# camara.net
KiCad netlist of a schematic drawn in EAGLE
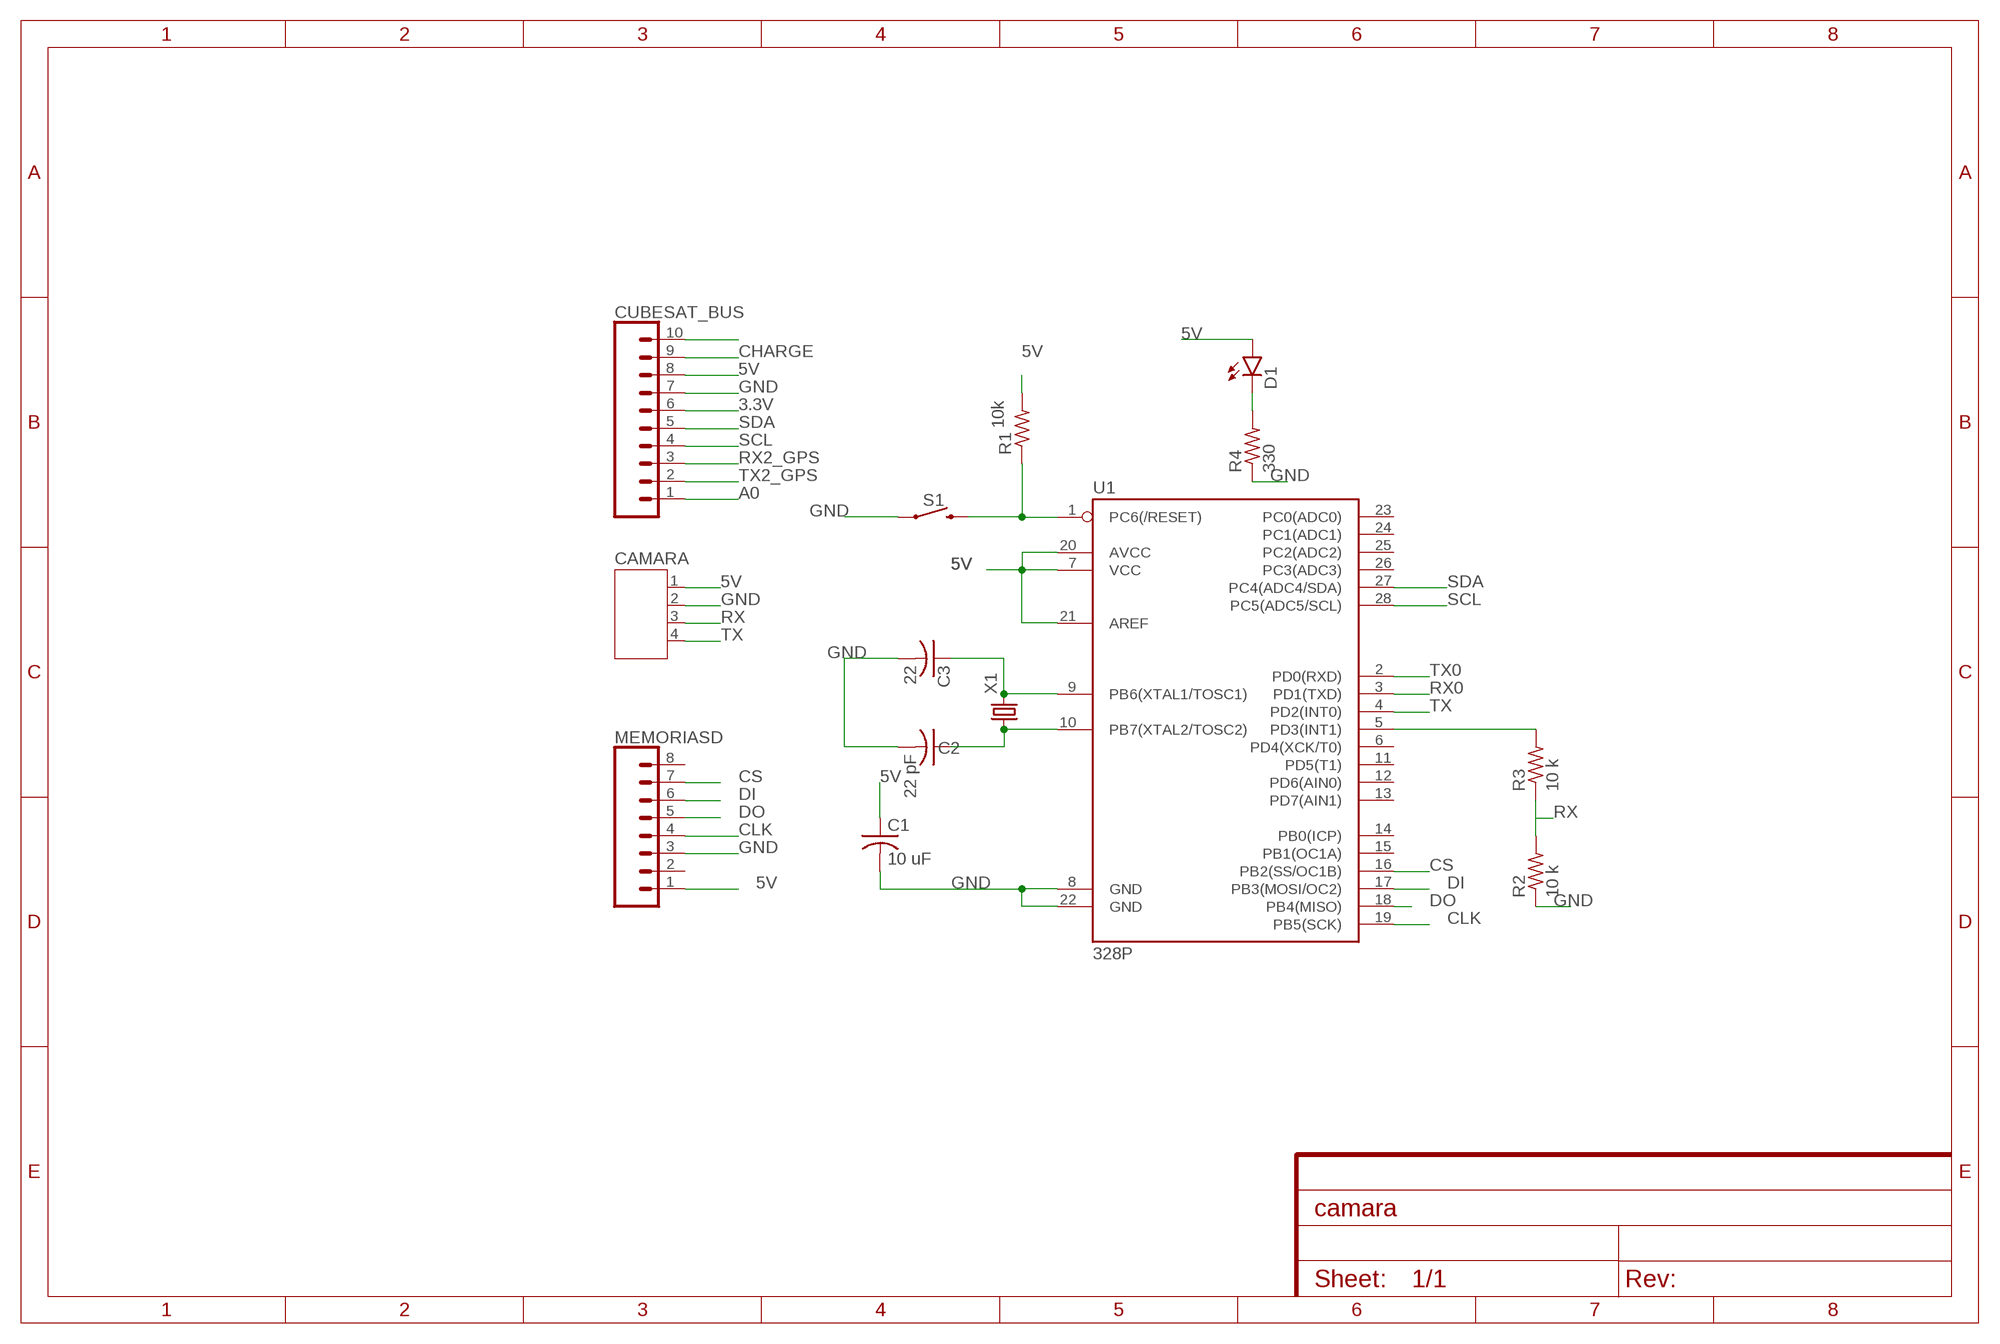
[diagram p0: schematic, sheet 1]

(export (version "E")
  (design (tool "Eeschema 10.0.6"))
  (components
    (comp (ref "C1")
      (value "10 uF")
      (footprint "eagle-import:C025-025X050")
      (libsource (lib "eagle-import") (part "C-US025-025X050"))
    )
    (comp (ref "C2")
      (value "22 pF")
      (footprint "eagle-import:C025-025X050")
      (libsource (lib "eagle-import") (part "C-US025-025X050"))
    )
    (comp (ref "C3")
      (value "22")
      (footprint "eagle-import:C025-025X050")
      (libsource (lib "eagle-import") (part "C-US025-025X050"))
    )
    (comp (ref "CAMARA")
      (value "JST-PH4")
      (footprint "eagle-import:JST-PH4")
      (libsource (lib "eagle-import") (part "JST-PH4"))
    )
    (comp (ref "CUBESAT_BUS")
      (value "CONN_10\"")
      (footprint "eagle-import:1X10")
      (libsource (lib "eagle-import") (part "CONN_10{dblquote}"))
    )
    (comp (ref "D1")
      (value "BEAGLEBONE_BLUE_LED-3MM-NO_SILK")
      (footprint "eagle-import:BEAGLEBONE_BLUE_BEAGLEBONE_BLUE_LED3MM-NS")
      (libsource (lib "eagle-import") (part "BEAGLEBONE_BLUE_LED-3MM-NO_SILK"))
    )
    (comp (ref "MEMORIASD")
      (value "CONN_08\"")
      (footprint "eagle-import:1X08")
      (libsource (lib "eagle-import") (part "CONN_08{dblquote}"))
    )
    (comp (ref "R1")
      (value "R-US_0204/7")
      (footprint "eagle-import:0204_7")
      (fields (field (name "SPICEPREFIX") "R") (field (name "SPICEPREFIX_1") "10k"))
      (libsource (lib "eagle-import") (part "R-US_0204/7"))
    )
    (comp (ref "R2")
      (value "10 k")
      (footprint "eagle-import:0204_7")
      (libsource (lib "eagle-import") (part "R-US_0204/7"))
    )
    (comp (ref "R3")
      (value "10 k")
      (footprint "eagle-import:0204_7")
      (libsource (lib "eagle-import") (part "R-US_0204/7"))
    )
    (comp (ref "R4")
      (value "330")
      (footprint "eagle-import:0204_7")
      (libsource (lib "eagle-import") (part "R-US_0204/7"))
    )
    (comp (ref "S1")
      (value "MOMENTARY-SWITCH-SPST-PTH-6.0MM")
      (footprint "eagle-import:TACTILE_SWITCH_PTH_6.0MM")
      (libsource (lib "eagle-import") (part "MOMENTARY-SWITCH-SPST-PTH-6.0MM"))
    )
    (comp (ref "U1")
      (value "328P")
      (footprint "eagle-import:DIP28")
      (libsource (lib "eagle-import") (part "ATMEGA328P_PDIP"))
    )
    (comp (ref "X1")
      (value "CRYSTALS-NOGND-HC49")
      (footprint "eagle-import:HC49")
      (fields (field (name "POPULARITY") "16MHZ"))
      (libsource (lib "eagle-import") (part "CRYSTALS-NOGND-HC49"))
    )
  )
  (nets
    (net (code "1") (name "/3.3V") (class "Default")
      (node (ref "CUBESAT_BUS") (pin "6") (pinfunction "6_6") (pintype "passive"))
    )
    (net (code "2") (name "/5V") (class "Default")
      (node (ref "C1") (pin "1") (pinfunction "1_1") (pintype "passive"))
      (node (ref "CAMARA") (pin "1") (pinfunction "1_1") (pintype "passive"))
      (node (ref "CUBESAT_BUS") (pin "8") (pinfunction "8_8") (pintype "passive"))
      (node (ref "D1") (pin "A") (pinfunction "A_A") (pintype "passive"))
      (node (ref "MEMORIASD") (pin "1") (pinfunction "1_1") (pintype "passive"))
      (node (ref "R1") (pin "2") (pinfunction "2_2") (pintype "passive"))
      (node (ref "U1") (pin "20") (pinfunction "AVCC_20") (pintype "bidirectional"))
      (node (ref "U1") (pin "21") (pinfunction "AREF_21") (pintype "bidirectional"))
      (node (ref "U1") (pin "7") (pinfunction "VCC_7") (pintype "bidirectional"))
    )
    (net (code "3") (name "/A0") (class "Default")
      (node (ref "CUBESAT_BUS") (pin "1") (pinfunction "1_1") (pintype "passive"))
    )
    (net (code "4") (name "/CHARGE") (class "Default")
      (node (ref "CUBESAT_BUS") (pin "9") (pinfunction "9_9") (pintype "passive"))
    )
    (net (code "5") (name "/CLK") (class "Default")
      (node (ref "MEMORIASD") (pin "4") (pinfunction "4_4") (pintype "passive"))
      (node (ref "U1") (pin "19") (pinfunction "PB5(SCK)_19") (pintype "bidirectional"))
    )
    (net (code "6") (name "/CS") (class "Default")
      (node (ref "MEMORIASD") (pin "7") (pinfunction "7_7") (pintype "passive"))
      (node (ref "U1") (pin "16") (pinfunction "PB2(SS/OC1B)_16") (pintype "bidirectional"))
    )
    (net (code "7") (name "/DI") (class "Default")
      (node (ref "MEMORIASD") (pin "6") (pinfunction "6_6") (pintype "passive"))
      (node (ref "U1") (pin "17") (pinfunction "PB3(MOSI/OC2)_17") (pintype "bidirectional"))
    )
    (net (code "8") (name "/DO") (class "Default")
      (node (ref "MEMORIASD") (pin "5") (pinfunction "5_5") (pintype "passive"))
      (node (ref "U1") (pin "18") (pinfunction "PB4(MISO)_18") (pintype "bidirectional"))
    )
    (net (code "9") (name "/GND") (class "Default")
      (node (ref "C1") (pin "2") (pinfunction "2_2") (pintype "passive"))
      (node (ref "C2") (pin "2") (pinfunction "2_2") (pintype "passive"))
      (node (ref "C3") (pin "2") (pinfunction "2_2") (pintype "passive"))
      (node (ref "CAMARA") (pin "2") (pinfunction "2_2") (pintype "passive"))
      (node (ref "CUBESAT_BUS") (pin "7") (pinfunction "7_7") (pintype "passive"))
      (node (ref "MEMORIASD") (pin "3") (pinfunction "3_3") (pintype "passive"))
      (node (ref "R2") (pin "1") (pinfunction "1_1") (pintype "passive"))
      (node (ref "R4") (pin "1") (pinfunction "1_1") (pintype "passive"))
      (node (ref "S1") (pin "1") (pinfunction "1_1") (pintype "passive"))
      (node (ref "U1") (pin "22") (pinfunction "GND_22") (pintype "bidirectional"))
      (node (ref "U1") (pin "8") (pinfunction "GND_8") (pintype "bidirectional"))
    )
    (net (code "10") (name "/RX") (class "Default")
      (node (ref "CAMARA") (pin "3") (pinfunction "3_3") (pintype "passive"))
      (node (ref "R2") (pin "2") (pinfunction "2_2") (pintype "passive"))
      (node (ref "R3") (pin "1") (pinfunction "1_1") (pintype "passive"))
    )
    (net (code "11") (name "/RX0") (class "Default")
      (node (ref "U1") (pin "3") (pinfunction "PD1(TXD)_3") (pintype "bidirectional"))
    )
    (net (code "12") (name "/RX2_GPS") (class "Default")
      (node (ref "CUBESAT_BUS") (pin "3") (pinfunction "3_3") (pintype "passive"))
    )
    (net (code "13") (name "/SCL") (class "Default")
      (node (ref "CUBESAT_BUS") (pin "4") (pinfunction "4_4") (pintype "passive"))
      (node (ref "U1") (pin "28") (pinfunction "PC5(ADC5/SCL)_28") (pintype "bidirectional"))
    )
    (net (code "14") (name "/SDA") (class "Default")
      (node (ref "CUBESAT_BUS") (pin "5") (pinfunction "5_5") (pintype "passive"))
      (node (ref "U1") (pin "27") (pinfunction "PC4(ADC4/SDA)_27") (pintype "bidirectional"))
    )
    (net (code "15") (name "/TX") (class "Default")
      (node (ref "CAMARA") (pin "4") (pinfunction "4_4") (pintype "passive"))
      (node (ref "U1") (pin "4") (pinfunction "PD2(INT0)_4") (pintype "bidirectional"))
    )
    (net (code "16") (name "/TX0") (class "Default")
      (node (ref "U1") (pin "2") (pinfunction "PD0(RXD)_2") (pintype "bidirectional"))
    )
    (net (code "17") (name "/TX2_GPS") (class "Default")
      (node (ref "CUBESAT_BUS") (pin "2") (pinfunction "2_2") (pintype "passive"))
    )
    (net (code "18") (name "Net-(D1-C)") (class "Default")
      (node (ref "D1") (pin "K") (pinfunction "C_K") (pintype "passive"))
      (node (ref "R4") (pin "2") (pinfunction "2_2") (pintype "passive"))
    )
    (net (code "19") (name "Net-(S1-2)") (class "Default")
      (node (ref "R1") (pin "1") (pinfunction "1_1") (pintype "passive"))
      (node (ref "S1") (pin "3") (pinfunction "2_3") (pintype "passive"))
      (node (ref "U1") (pin "1") (pinfunction "PC6(/RESET)_1") (pintype "bidirectional"))
    )
    (net (code "20") (name "Net-(U1-PB6(XTAL1{slash}TOSC1))") (class "Default")
      (node (ref "C3") (pin "1") (pinfunction "1_1") (pintype "passive"))
      (node (ref "U1") (pin "9") (pinfunction "PB6(XTAL1/TOSC1)_9") (pintype "bidirectional"))
      (node (ref "X1") (pin "2") (pinfunction "2_2") (pintype "passive"))
    )
    (net (code "21") (name "Net-(U1-PB7(XTAL2{slash}TOSC2))") (class "Default")
      (node (ref "C2") (pin "1") (pinfunction "1_1") (pintype "passive"))
      (node (ref "U1") (pin "10") (pinfunction "PB7(XTAL2/TOSC2)_10") (pintype "bidirectional"))
      (node (ref "X1") (pin "1") (pinfunction "1_1") (pintype "passive"))
    )
    (net (code "22") (name "Net-(U1-PD3(INT1))") (class "Default")
      (node (ref "R3") (pin "2") (pinfunction "2_2") (pintype "passive"))
      (node (ref "U1") (pin "5") (pinfunction "PD3(INT1)_5") (pintype "bidirectional"))
    )
    (net (code "23") (name "unconnected-(CUBESAT_BUS-Pad10)") (class "Default")
      (node (ref "CUBESAT_BUS") (pin "10") (pinfunction "10_10") (pintype "passive"))
    )
    (net (code "24") (name "unconnected-(MEMORIASD-Pad2)") (class "Default")
      (node (ref "MEMORIASD") (pin "2") (pinfunction "2_2") (pintype "passive"))
    )
    (net (code "25") (name "unconnected-(MEMORIASD-Pad8)") (class "Default")
      (node (ref "MEMORIASD") (pin "8") (pinfunction "8_8") (pintype "passive"))
    )
    (net (code "26") (name "unconnected-(U1-PB0(ICP)-Pad14)") (class "Default")
      (node (ref "U1") (pin "14") (pinfunction "PB0(ICP)_14") (pintype "bidirectional"))
    )
    (net (code "27") (name "unconnected-(U1-PB1(OC1A)-Pad15)") (class "Default")
      (node (ref "U1") (pin "15") (pinfunction "PB1(OC1A)_15") (pintype "bidirectional"))
    )
    (net (code "28") (name "unconnected-(U1-PC0(ADC0)-Pad23)") (class "Default")
      (node (ref "U1") (pin "23") (pinfunction "PC0(ADC0)_23") (pintype "bidirectional"))
    )
    (net (code "29") (name "unconnected-(U1-PC1(ADC1)-Pad24)") (class "Default")
      (node (ref "U1") (pin "24") (pinfunction "PC1(ADC1)_24") (pintype "bidirectional"))
    )
    (net (code "30") (name "unconnected-(U1-PC2(ADC2)-Pad25)") (class "Default")
      (node (ref "U1") (pin "25") (pinfunction "PC2(ADC2)_25") (pintype "bidirectional"))
    )
    (net (code "31") (name "unconnected-(U1-PC3(ADC3)-Pad26)") (class "Default")
      (node (ref "U1") (pin "26") (pinfunction "PC3(ADC3)_26") (pintype "bidirectional"))
    )
    (net (code "32") (name "unconnected-(U1-PD4(XCK{slash}T0)-Pad6)") (class "Default")
      (node (ref "U1") (pin "6") (pinfunction "PD4(XCK/T0)_6") (pintype "bidirectional"))
    )
    (net (code "33") (name "unconnected-(U1-PD5(T1)-Pad11)") (class "Default")
      (node (ref "U1") (pin "11") (pinfunction "PD5(T1)_11") (pintype "bidirectional"))
    )
    (net (code "34") (name "unconnected-(U1-PD6(AIN0)-Pad12)") (class "Default")
      (node (ref "U1") (pin "12") (pinfunction "PD6(AIN0)_12") (pintype "bidirectional"))
    )
    (net (code "35") (name "unconnected-(U1-PD7(AIN1)-Pad13)") (class "Default")
      (node (ref "U1") (pin "13") (pinfunction "PD7(AIN1)_13") (pintype "bidirectional"))
    )
  )
)
